# Board1.net
KiCad netlist of a schematic drawn in EasyEDA Pro
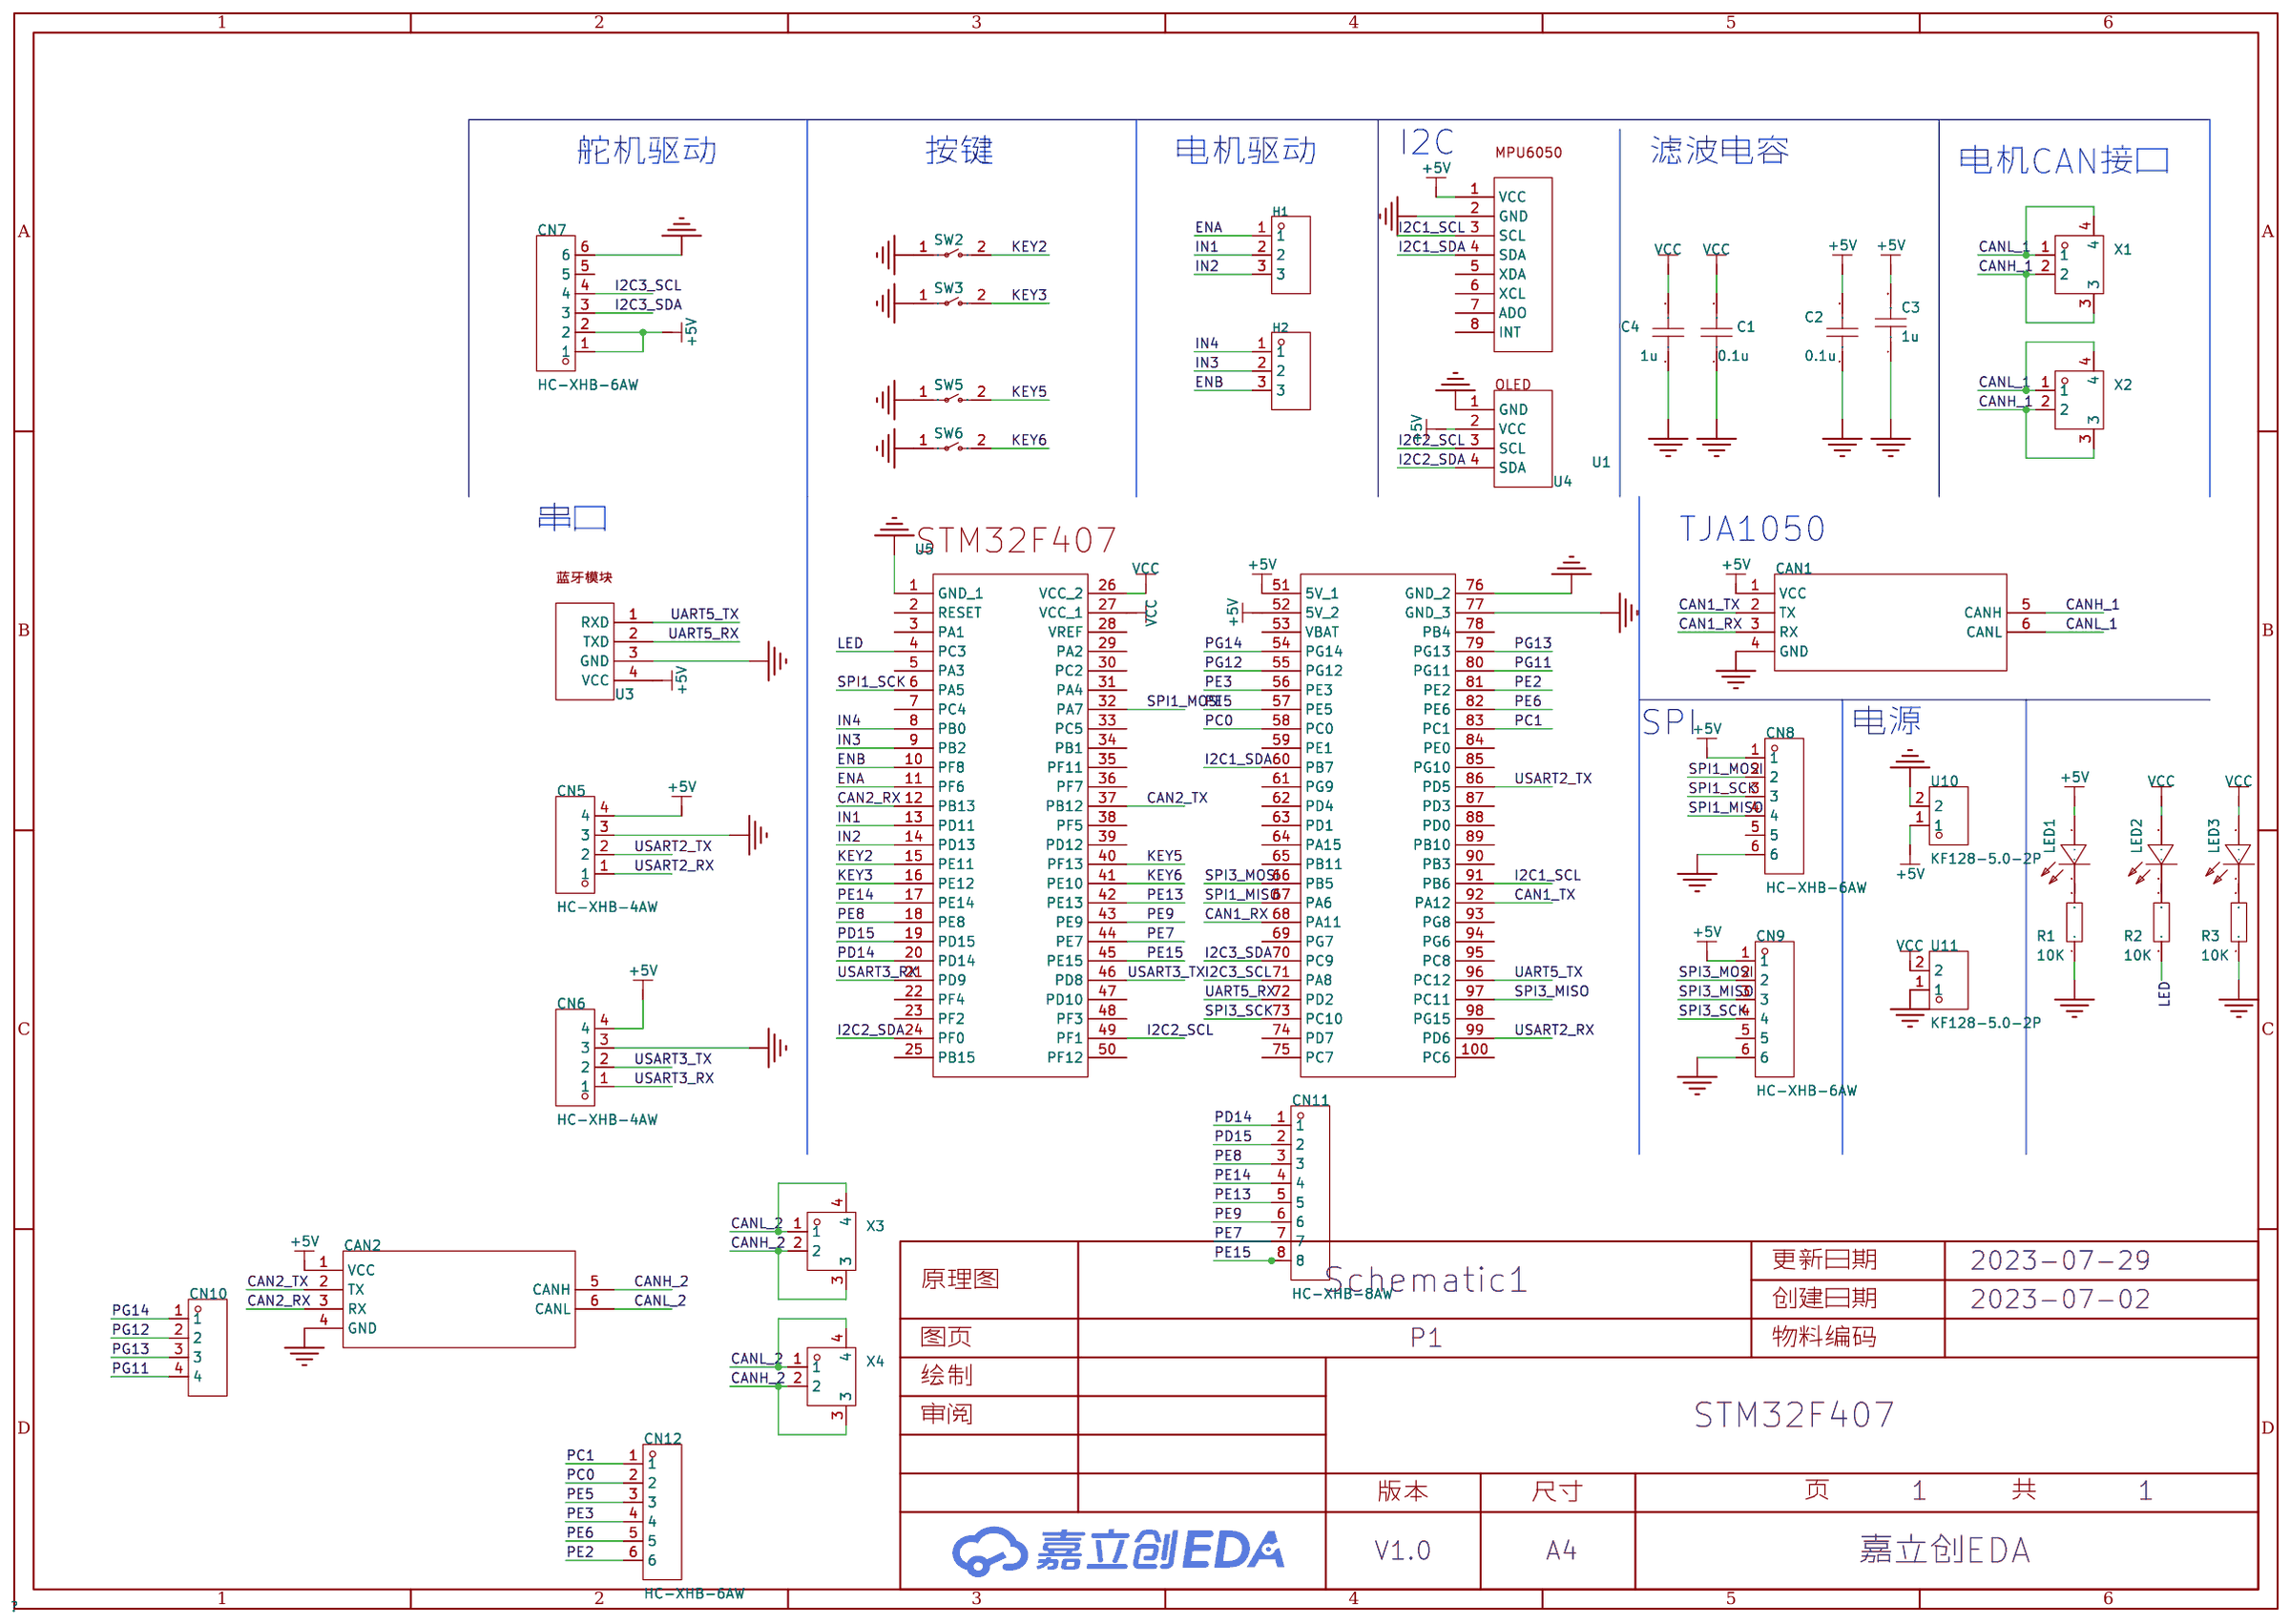
[diagram p0: schematic sheet]

(export (version "E")
  (design (tool "Eeschema 10.0.6"))
  (components
    (comp (ref "C1")
      (value "0.1u")
      (footprint "easyedapro:C0603")
      (libsource (lib "easyedapro") (part "CapAcitance"))
    )
    (comp (ref "C2")
      (value "0.1u")
      (footprint "easyedapro:C0603")
      (libsource (lib "easyedapro") (part "CapAcitance"))
    )
    (comp (ref "C3")
      (value "1u")
      (footprint "easyedapro:C0603")
      (libsource (lib "easyedapro") (part "CapAcitance"))
    )
    (comp (ref "C4")
      (value "1u")
      (footprint "easyedapro:C0603")
      (libsource (lib "easyedapro") (part "CapAcitance"))
    )
    (comp (ref "CAN1")
      (value "~")
      (footprint "easyedapro:CAN模块")
      (libsource (lib "easyedapro") (part "CAN模块"))
    )
    (comp (ref "CAN2")
      (value "~")
      (footprint "easyedapro:CAN模块")
      (libsource (lib "easyedapro") (part "CAN模块"))
    )
    (comp (ref "CN5")
      (value "HC-XHB-4AW")
      (footprint "easyedapro:CONN-TH_4P-P2.5_HCTL_HC-XHB-4AW")
      (description "参考系列:-;间距:2.5mm;插针结构:1x4P;排数:1;每排PIN数:4;行距:-;公母:公型插针;安装方式:弯插;额定电流:3A;工作温度范围:-25°C~+85°C;")
      (fields (field (name "Manufacturer") "HCTL(华灿天禄)"))
      (libsource (lib "easyedapro") (part "HC-XHB-4AW"))
    )
    (comp (ref "CN6")
      (value "HC-XHB-4AW")
      (footprint "easyedapro:CONN-TH_4P-P2.5_HCTL_HC-XHB-4AW")
      (description "参考系列:-;间距:2.5mm;插针结构:1x4P;排数:1;每排PIN数:4;行距:-;公母:公型插针;安装方式:弯插;额定电流:3A;工作温度范围:-25°C~+85°C;")
      (fields (field (name "Manufacturer") "HCTL(华灿天禄)"))
      (libsource (lib "easyedapro") (part "HC-XHB-4AW"))
    )
    (comp (ref "CN7")
      (value "HC-XHB-6AW")
      (footprint "easyedapro:CONN-TH_6P-P2.50_HCTL_HC-XHB-6AW")
      (description "参考系列:-;间距:2.5mm;插针结构:1x6P;排数:1;每排PIN数:6;行距:-;公母:公型插针;安装方式:弯插;额定电流:3A;工作温度范围:-25°C~+85°C;")
      (fields (field (name "Manufacturer") "HCTL(华灿天禄)"))
      (libsource (lib "easyedapro") (part "HC-XHB-6AW"))
    )
    (comp (ref "CN8")
      (value "HC-XHB-6AW")
      (footprint "easyedapro:CONN-TH_6P-P2.50_HCTL_HC-XHB-6AW")
      (description "参考系列:-;间距:2.5mm;插针结构:1x6P;排数:1;每排PIN数:6;行距:-;公母:公型插针;安装方式:弯插;额定电流:3A;工作温度范围:-25°C~+85°C;")
      (fields (field (name "Manufacturer") "HCTL(华灿天禄)"))
      (libsource (lib "easyedapro") (part "HC-XHB-6AW"))
    )
    (comp (ref "CN9")
      (value "HC-XHB-6AW")
      (footprint "easyedapro:CONN-TH_6P-P2.50_HCTL_HC-XHB-6AW")
      (description "参考系列:-;间距:2.5mm;插针结构:1x6P;排数:1;每排PIN数:6;行距:-;公母:公型插针;安装方式:弯插;额定电流:3A;工作温度范围:-25°C~+85°C;")
      (fields (field (name "Manufacturer") "HCTL(华灿天禄)"))
      (libsource (lib "easyedapro") (part "HC-XHB-6AW"))
    )
    (comp (ref "CN10")
      (value "HC-XHB-4AW")
      (footprint "easyedapro:CONN-TH_4P-P2.5_HCTL_HC-XHB-4AW")
      (description "参考系列:-;间距:2.5mm;插针结构:1x4P;排数:1;每排PIN数:4;行距:-;公母:公型插针;安装方式:弯插;额定电流:3A;工作温度范围:-25°C~+85°C;")
      (fields (field (name "Manufacturer") "HCTL(华灿天禄)"))
      (libsource (lib "easyedapro") (part "HC-XHB-4AW"))
    )
    (comp (ref "CN11")
      (value "HC-XHB-8AW")
      (footprint "easyedapro:CONN-TH_HC-XHB-8AW")
      (description "参考系列:-;间距:2.5mm;插针结构:1x8P;排数:1;每排PIN数:8;行距:-;公母:公型插针;安装方式:弯插;额定电流:3A;工作温度范围:-25°C~+85°C;")
      (fields (field (name "Manufacturer") "HCTL(华灿天禄)"))
      (libsource (lib "easyedapro") (part "HC-XHB-8AW"))
    )
    (comp (ref "CN12")
      (value "HC-XHB-6AW")
      (footprint "easyedapro:CONN-TH_6P-P2.50_HCTL_HC-XHB-6AW")
      (description "参考系列:-;间距:2.5mm;插针结构:1x6P;排数:1;每排PIN数:6;行距:-;公母:公型插针;安装方式:弯插;额定电流:3A;工作温度范围:-25°C~+85°C;")
      (fields (field (name "Manufacturer") "HCTL(华灿天禄)"))
      (libsource (lib "easyedapro") (part "HC-XHB-6AW"))
    )
    (comp (ref "H1")
      (value "~")
      (footprint "easyedapro:HDR-TH_3P-P2.54-V-F")
      (libsource (lib "easyedapro") (part "PM254V-11-03-H85"))
    )
    (comp (ref "H2")
      (value "~")
      (footprint "easyedapro:HDR-TH_3P-P2.54-V-F")
      (libsource (lib "easyedapro") (part "PM254V-11-03-H85"))
    )
    (comp (ref "LED1")
      (value "NCD0805R1")
      (footprint "easyedapro:LED0805-RD_RED")
      (description "发光颜色:红灯;")
      (fields (field (name "Manufacturer") "国星光电"))
      (libsource (lib "easyedapro") (part "FC-2012HRK-620D"))
    )
    (comp (ref "LED2")
      (value "NCD0805R1")
      (footprint "easyedapro:LED0805-RD_RED")
      (description "发光颜色:红灯;")
      (fields (field (name "Manufacturer") "国星光电"))
      (libsource (lib "easyedapro") (part "FC-2012HRK-620D"))
    )
    (comp (ref "LED3")
      (value "NCD0805R1")
      (footprint "easyedapro:LED0805-RD_RED")
      (description "发光颜色:红灯;")
      (fields (field (name "Manufacturer") "国星光电"))
      (libsource (lib "easyedapro") (part "FC-2012HRK-620D"))
    )
    (comp (ref "R1") (value "10K") (footprint "easyedapro:R0603") (libsource (lib "easyedapro") (part "电阻")))
    (comp (ref "R2") (value "10K") (footprint "easyedapro:R0603") (libsource (lib "easyedapro") (part "电阻")))
    (comp (ref "R3") (value "10K") (footprint "easyedapro:R0603") (libsource (lib "easyedapro") (part "电阻")))
    (comp (ref "SW2")
      (value "TS-1007S-AR02516")
      (footprint "easyedapro:SW-SMD_L6.1-W3.6-LS7.9")
      (description "触点电流:50mA;额定电压(DC):12V;绝缘电阻:100MΩ;电路结构:单刀单掷;安装方式:立贴;作用力:160gf@±50gf;机械寿命:5万次;带支架:否;")
      (fields (field (name "Manufacturer") "XUNPU(讯普)"))
      (libsource (lib "easyedapro") (part "TS-1007S-AR02516"))
    )
    (comp (ref "SW3")
      (value "TS-1007S-AR02516")
      (footprint "easyedapro:SW-SMD_L6.1-W3.6-LS7.9")
      (description "触点电流:50mA;额定电压(DC):12V;绝缘电阻:100MΩ;电路结构:单刀单掷;安装方式:立贴;作用力:160gf@±50gf;机械寿命:5万次;带支架:否;")
      (fields (field (name "Manufacturer") "XUNPU(讯普)"))
      (libsource (lib "easyedapro") (part "TS-1007S-AR02516"))
    )
    (comp (ref "SW5")
      (value "TS-1007S-AR02516")
      (footprint "easyedapro:SW-SMD_L6.1-W3.6-LS7.9")
      (description "触点电流:50mA;额定电压(DC):12V;绝缘电阻:100MΩ;电路结构:单刀单掷;安装方式:立贴;作用力:160gf@±50gf;机械寿命:5万次;带支架:否;")
      (fields (field (name "Manufacturer") "XUNPU(讯普)"))
      (libsource (lib "easyedapro") (part "TS-1007S-AR02516"))
    )
    (comp (ref "SW6")
      (value "TS-1007S-AR02516")
      (footprint "easyedapro:SW-SMD_L6.1-W3.6-LS7.9")
      (description "触点电流:50mA;额定电压(DC):12V;绝缘电阻:100MΩ;电路结构:单刀单掷;安装方式:立贴;作用力:160gf@±50gf;机械寿命:5万次;带支架:否;")
      (fields (field (name "Manufacturer") "XUNPU(讯普)"))
      (libsource (lib "easyedapro") (part "TS-1007S-AR02516"))
    )
    (comp (ref "U1")
      (value "~")
      (footprint "easyedapro:MPU6050")
      (libsource (lib "easyedapro") (part "MPU6050"))
    )
    (comp (ref "U3") (value "~") (footprint "easyedapro:蓝牙模块") (libsource (lib "easyedapro") (part "蓝牙模块")))
    (comp (ref "U4") (value "~") (footprint "easyedapro:OLED") (libsource (lib "easyedapro") (part "OLED")))
    (comp (ref "U5")
      (value "~")
      (footprint "easyedapro:CORE BORED")
      (libsource (lib "easyedapro") (part "CORE BORED"))
    )
    (comp (ref "U10")
      (value "KF128-5.0-2P")
      (footprint "easyedapro:CONN-TH_P5.00_KF128-5.0-2P")
      (fields (field (name "Manufacturer") "KEFA(科发)"))
      (libsource (lib "easyedapro") (part "KF128-5.0-2P"))
    )
    (comp (ref "U11")
      (value "KF128-5.0-2P")
      (footprint "easyedapro:CONN-TH_P5.00_KF128-5.0-2P")
      (fields (field (name "Manufacturer") "KEFA(科发)"))
      (libsource (lib "easyedapro") (part "KF128-5.0-2P"))
    )
    (comp (ref "X1")
      (value "GH125-S02DCA-00")
      (footprint "easyedapro:CONN-SMD_2P-P1.25_JUSHUO_GH125-S02DCA-00")
      (description "参考系列:-;间距:1.25mm;插针结构:1x2P;排数:1;每排PIN数:2;行距:-;公母:公型插针;安装方式:卧贴;额定电流:1A;工作温度范围:-25°C~+85°C;")
      (fields (field (name "Manufacturer") "JS(钜硕电子)"))
      (libsource (lib "easyedapro") (part "GH125-S02DCA-00"))
    )
    (comp (ref "X2")
      (value "GH125-S02DCA-00")
      (footprint "easyedapro:CONN-SMD_2P-P1.25_JUSHUO_GH125-S02DCA-00")
      (description "参考系列:-;间距:1.25mm;插针结构:1x2P;排数:1;每排PIN数:2;行距:-;公母:公型插针;安装方式:卧贴;额定电流:1A;工作温度范围:-25°C~+85°C;")
      (fields (field (name "Manufacturer") "JS(钜硕电子)"))
      (libsource (lib "easyedapro") (part "GH125-S02DCA-00"))
    )
    (comp (ref "X3")
      (value "GH125-S02DCA-00")
      (footprint "easyedapro:CONN-SMD_2P-P1.25_JUSHUO_GH125-S02DCA-00")
      (description "参考系列:-;间距:1.25mm;插针结构:1x2P;排数:1;每排PIN数:2;行距:-;公母:公型插针;安装方式:卧贴;额定电流:1A;工作温度范围:-25°C~+85°C;")
      (fields (field (name "Manufacturer") "JS(钜硕电子)"))
      (libsource (lib "easyedapro") (part "GH125-S02DCA-00"))
    )
    (comp (ref "X4")
      (value "GH125-S02DCA-00")
      (footprint "easyedapro:CONN-SMD_2P-P1.25_JUSHUO_GH125-S02DCA-00")
      (description "参考系列:-;间距:1.25mm;插针结构:1x2P;排数:1;每排PIN数:2;行距:-;公母:公型插针;安装方式:卧贴;额定电流:1A;工作温度范围:-25°C~+85°C;")
      (fields (field (name "Manufacturer") "JS(钜硕电子)"))
      (libsource (lib "easyedapro") (part "GH125-S02DCA-00"))
    )
  )
  (nets
    (net (code "1") (name "+5V") (class "Default")
      (node (ref "C2") (pin "2") (pinfunction "2_2") (pintype "input"))
      (node (ref "C3") (pin "2") (pinfunction "2_2") (pintype "input"))
      (node (ref "CAN1") (pin "1") (pinfunction "VCC_1") (pintype "input"))
      (node (ref "CAN2") (pin "1") (pinfunction "VCC_1") (pintype "input"))
      (node (ref "CN5") (pin "4") (pinfunction "4_4") (pintype "input"))
      (node (ref "CN6") (pin "4") (pinfunction "4_4") (pintype "input"))
      (node (ref "CN7") (pin "1") (pinfunction "1_1") (pintype "input"))
      (node (ref "CN7") (pin "2") (pinfunction "2_2") (pintype "input"))
      (node (ref "CN8") (pin "1") (pinfunction "1_1") (pintype "input"))
      (node (ref "CN9") (pin "1") (pinfunction "1_1") (pintype "input"))
      (node (ref "LED1") (pin "2") (pinfunction "+_2") (pintype "input"))
      (node (ref "U1") (pin "1") (pinfunction "VCC_1") (pintype "input"))
      (node (ref "U10") (pin "1") (pinfunction "1_1") (pintype "input"))
      (node (ref "U3") (pin "4") (pinfunction "VCC_4") (pintype "input"))
      (node (ref "U4") (pin "2") (pinfunction "VCC_2") (pintype "input"))
      (node (ref "U5") (pin "51") (pinfunction "5V_1_51") (pintype "input"))
      (node (ref "U5") (pin "52") (pinfunction "5V_2_52") (pintype "input"))
    )
    (net (code "2") (name "/CAN1_RX") (class "Default")
      (node (ref "CAN1") (pin "3") (pinfunction "RX_3") (pintype "input"))
      (node (ref "U5") (pin "68") (pinfunction "PA11_68") (pintype "input"))
    )
    (net (code "3") (name "/CAN1_TX") (class "Default")
      (node (ref "CAN1") (pin "2") (pinfunction "TX_2") (pintype "input"))
      (node (ref "U5") (pin "92") (pinfunction "PA12_92") (pintype "input"))
    )
    (net (code "4") (name "/CAN2_RX") (class "Default")
      (node (ref "CAN2") (pin "3") (pinfunction "RX_3") (pintype "input"))
      (node (ref "U5") (pin "12") (pinfunction "PB13_12") (pintype "input"))
    )
    (net (code "5") (name "/CAN2_TX") (class "Default")
      (node (ref "CAN2") (pin "2") (pinfunction "TX_2") (pintype "input"))
      (node (ref "U5") (pin "37") (pinfunction "PB12_37") (pintype "input"))
    )
    (net (code "6") (name "/CANH_1") (class "Default")
      (node (ref "CAN1") (pin "5") (pinfunction "CANH_5") (pintype "input"))
      (node (ref "X1") (pin "2") (pinfunction "2_2") (pintype "input"))
      (node (ref "X1") (pin "3") (pinfunction "3_3") (pintype "input"))
      (node (ref "X2") (pin "2") (pinfunction "2_2") (pintype "input"))
      (node (ref "X2") (pin "3") (pinfunction "3_3") (pintype "input"))
    )
    (net (code "7") (name "/CANH_2") (class "Default")
      (node (ref "CAN2") (pin "5") (pinfunction "CANH_5") (pintype "input"))
      (node (ref "X3") (pin "2") (pinfunction "2_2") (pintype "input"))
      (node (ref "X3") (pin "3") (pinfunction "3_3") (pintype "input"))
      (node (ref "X4") (pin "2") (pinfunction "2_2") (pintype "input"))
      (node (ref "X4") (pin "3") (pinfunction "3_3") (pintype "input"))
    )
    (net (code "8") (name "/CANL_1") (class "Default")
      (node (ref "CAN1") (pin "6") (pinfunction "CANL_6") (pintype "input"))
      (node (ref "X1") (pin "1") (pinfunction "1_1") (pintype "input"))
      (node (ref "X1") (pin "4") (pinfunction "4_4") (pintype "input"))
      (node (ref "X2") (pin "1") (pinfunction "1_1") (pintype "input"))
      (node (ref "X2") (pin "4") (pinfunction "4_4") (pintype "input"))
    )
    (net (code "9") (name "/CANL_2") (class "Default")
      (node (ref "CAN2") (pin "6") (pinfunction "CANL_6") (pintype "input"))
      (node (ref "X3") (pin "1") (pinfunction "1_1") (pintype "input"))
      (node (ref "X3") (pin "4") (pinfunction "4_4") (pintype "input"))
      (node (ref "X4") (pin "1") (pinfunction "1_1") (pintype "input"))
      (node (ref "X4") (pin "4") (pinfunction "4_4") (pintype "input"))
    )
    (net (code "10") (name "/ENA") (class "Default")
      (node (ref "H1") (pin "1") (pinfunction "1_1") (pintype "input"))
      (node (ref "U5") (pin "11") (pinfunction "PF6_11") (pintype "input"))
    )
    (net (code "11") (name "/ENB") (class "Default")
      (node (ref "H2") (pin "3") (pinfunction "3_3") (pintype "input"))
      (node (ref "U5") (pin "10") (pinfunction "PF8_10") (pintype "input"))
    )
    (net (code "12") (name "/I2C1_SCL") (class "Default")
      (node (ref "U1") (pin "3") (pinfunction "SCL_3") (pintype "input"))
      (node (ref "U5") (pin "91") (pinfunction "PB6_91") (pintype "input"))
    )
    (net (code "13") (name "/I2C1_SDA") (class "Default")
      (node (ref "U1") (pin "4") (pinfunction "SDA_4") (pintype "input"))
      (node (ref "U5") (pin "60") (pinfunction "PB7_60") (pintype "input"))
    )
    (net (code "14") (name "/I2C2_SCL") (class "Default")
      (node (ref "U4") (pin "3") (pinfunction "SCL_3") (pintype "input"))
      (node (ref "U5") (pin "49") (pinfunction "PF1_49") (pintype "input"))
    )
    (net (code "15") (name "/I2C2_SDA") (class "Default")
      (node (ref "U4") (pin "4") (pinfunction "SDA_4") (pintype "input"))
      (node (ref "U5") (pin "24") (pinfunction "PF0_24") (pintype "input"))
    )
    (net (code "16") (name "/I2C3_SCL") (class "Default")
      (node (ref "CN7") (pin "4") (pinfunction "4_4") (pintype "input"))
      (node (ref "U5") (pin "71") (pinfunction "PA8_71") (pintype "input"))
    )
    (net (code "17") (name "/I2C3_SDA") (class "Default")
      (node (ref "CN7") (pin "3") (pinfunction "3_3") (pintype "input"))
      (node (ref "U5") (pin "70") (pinfunction "PC9_70") (pintype "input"))
    )
    (net (code "18") (name "/IN1") (class "Default")
      (node (ref "H1") (pin "2") (pinfunction "2_2") (pintype "input"))
      (node (ref "U5") (pin "13") (pinfunction "PD11_13") (pintype "input"))
    )
    (net (code "19") (name "/IN2") (class "Default")
      (node (ref "H1") (pin "3") (pinfunction "3_3") (pintype "input"))
      (node (ref "U5") (pin "14") (pinfunction "PD13_14") (pintype "input"))
    )
    (net (code "20") (name "/IN3") (class "Default")
      (node (ref "H2") (pin "2") (pinfunction "2_2") (pintype "input"))
      (node (ref "U5") (pin "9") (pinfunction "PB2_9") (pintype "input"))
    )
    (net (code "21") (name "/IN4") (class "Default")
      (node (ref "H2") (pin "1") (pinfunction "1_1") (pintype "input"))
      (node (ref "U5") (pin "8") (pinfunction "PB0_8") (pintype "input"))
    )
    (net (code "22") (name "/KEY2") (class "Default")
      (node (ref "SW2") (pin "2") (pinfunction "2_2") (pintype "input"))
      (node (ref "U5") (pin "15") (pinfunction "PE11_15") (pintype "input"))
    )
    (net (code "23") (name "/KEY3") (class "Default")
      (node (ref "SW3") (pin "2") (pinfunction "2_2") (pintype "input"))
      (node (ref "U5") (pin "16") (pinfunction "PE12_16") (pintype "input"))
    )
    (net (code "24") (name "/KEY5") (class "Default")
      (node (ref "SW5") (pin "2") (pinfunction "2_2") (pintype "input"))
      (node (ref "U5") (pin "40") (pinfunction "PF13_40") (pintype "input"))
    )
    (net (code "25") (name "/KEY6") (class "Default")
      (node (ref "SW6") (pin "2") (pinfunction "2_2") (pintype "input"))
      (node (ref "U5") (pin "41") (pinfunction "PE10_41") (pintype "input"))
    )
    (net (code "26") (name "/LED") (class "Default")
      (node (ref "R2") (pin "1") (pinfunction "1_1") (pintype "input"))
      (node (ref "U5") (pin "4") (pinfunction "PC3_4") (pintype "input"))
    )
    (net (code "27") (name "/PC0") (class "Default")
      (node (ref "CN12") (pin "2") (pinfunction "2_2") (pintype "input"))
      (node (ref "U5") (pin "58") (pinfunction "PC0_58") (pintype "input"))
    )
    (net (code "28") (name "/PC1") (class "Default")
      (node (ref "CN12") (pin "1") (pinfunction "1_1") (pintype "input"))
      (node (ref "U5") (pin "83") (pinfunction "PC1_83") (pintype "input"))
    )
    (net (code "29") (name "/PD14") (class "Default")
      (node (ref "CN11") (pin "1") (pinfunction "1_1") (pintype "input"))
      (node (ref "U5") (pin "20") (pinfunction "PD14_20") (pintype "input"))
    )
    (net (code "30") (name "/PD15") (class "Default")
      (node (ref "CN11") (pin "2") (pinfunction "2_2") (pintype "input"))
      (node (ref "U5") (pin "19") (pinfunction "PD15_19") (pintype "input"))
    )
    (net (code "31") (name "/PE2") (class "Default")
      (node (ref "CN12") (pin "6") (pinfunction "6_6") (pintype "input"))
      (node (ref "U5") (pin "81") (pinfunction "PE2_81") (pintype "input"))
    )
    (net (code "32") (name "/PE3") (class "Default")
      (node (ref "CN12") (pin "4") (pinfunction "4_4") (pintype "input"))
      (node (ref "U5") (pin "56") (pinfunction "PE3_56") (pintype "input"))
    )
    (net (code "33") (name "/PE5") (class "Default")
      (node (ref "CN12") (pin "3") (pinfunction "3_3") (pintype "input"))
      (node (ref "U5") (pin "57") (pinfunction "PE5_57") (pintype "input"))
    )
    (net (code "34") (name "/PE6") (class "Default")
      (node (ref "CN12") (pin "5") (pinfunction "5_5") (pintype "input"))
      (node (ref "U5") (pin "82") (pinfunction "PE6_82") (pintype "input"))
    )
    (net (code "35") (name "/PE7") (class "Default")
      (node (ref "CN11") (pin "7") (pinfunction "7_7") (pintype "input"))
      (node (ref "U5") (pin "44") (pinfunction "PE7_44") (pintype "input"))
    )
    (net (code "36") (name "/PE8") (class "Default")
      (node (ref "CN11") (pin "3") (pinfunction "3_3") (pintype "input"))
      (node (ref "U5") (pin "18") (pinfunction "PE8_18") (pintype "input"))
    )
    (net (code "37") (name "/PE9") (class "Default")
      (node (ref "CN11") (pin "6") (pinfunction "6_6") (pintype "input"))
      (node (ref "U5") (pin "43") (pinfunction "PE9_43") (pintype "input"))
    )
    (net (code "38") (name "/PE13") (class "Default")
      (node (ref "CN11") (pin "5") (pinfunction "5_5") (pintype "input"))
      (node (ref "U5") (pin "42") (pinfunction "PE13_42") (pintype "input"))
    )
    (net (code "39") (name "/PE14") (class "Default")
      (node (ref "CN11") (pin "4") (pinfunction "4_4") (pintype "input"))
      (node (ref "U5") (pin "17") (pinfunction "PE14_17") (pintype "input"))
    )
    (net (code "40") (name "/PE15") (class "Default")
      (node (ref "CN11") (pin "8") (pinfunction "8_8") (pintype "input"))
      (node (ref "U5") (pin "45") (pinfunction "PE15_45") (pintype "input"))
    )
    (net (code "41") (name "/PG11") (class "Default")
      (node (ref "CN10") (pin "4") (pinfunction "4_4") (pintype "input"))
      (node (ref "U5") (pin "80") (pinfunction "PG11_80") (pintype "input"))
    )
    (net (code "42") (name "/PG12") (class "Default")
      (node (ref "CN10") (pin "2") (pinfunction "2_2") (pintype "input"))
      (node (ref "U5") (pin "55") (pinfunction "PG12_55") (pintype "input"))
    )
    (net (code "43") (name "/PG13") (class "Default")
      (node (ref "CN10") (pin "3") (pinfunction "3_3") (pintype "input"))
      (node (ref "U5") (pin "79") (pinfunction "PG13_79") (pintype "input"))
    )
    (net (code "44") (name "/PG14") (class "Default")
      (node (ref "CN10") (pin "1") (pinfunction "1_1") (pintype "input"))
      (node (ref "U5") (pin "54") (pinfunction "PG14_54") (pintype "input"))
    )
    (net (code "45") (name "/SPI1_MISO") (class "Default")
      (node (ref "CN8") (pin "4") (pinfunction "4_4") (pintype "input"))
      (node (ref "U5") (pin "67") (pinfunction "PA6_67") (pintype "input"))
    )
    (net (code "46") (name "/SPI1_MOSI") (class "Default")
      (node (ref "CN8") (pin "2") (pinfunction "2_2") (pintype "input"))
      (node (ref "U5") (pin "32") (pinfunction "PA7_32") (pintype "input"))
    )
    (net (code "47") (name "/SPI1_SCK") (class "Default")
      (node (ref "CN8") (pin "3") (pinfunction "3_3") (pintype "input"))
      (node (ref "U5") (pin "6") (pinfunction "PA5_6") (pintype "input"))
    )
    (net (code "48") (name "/SPI3_MISO") (class "Default")
      (node (ref "CN9") (pin "3") (pinfunction "3_3") (pintype "input"))
      (node (ref "U5") (pin "97") (pinfunction "PC11_97") (pintype "input"))
    )
    (net (code "49") (name "/SPI3_MOSI") (class "Default")
      (node (ref "CN9") (pin "2") (pinfunction "2_2") (pintype "input"))
      (node (ref "U5") (pin "66") (pinfunction "PB5_66") (pintype "input"))
    )
    (net (code "50") (name "/SPI3_SCK") (class "Default")
      (node (ref "CN9") (pin "4") (pinfunction "4_4") (pintype "input"))
      (node (ref "U5") (pin "73") (pinfunction "PC10_73") (pintype "input"))
    )
    (net (code "51") (name "/UART5_RX") (class "Default")
      (node (ref "U3") (pin "2") (pinfunction "TXD_2") (pintype "input"))
      (node (ref "U5") (pin "72") (pinfunction "PD2_72") (pintype "input"))
    )
    (net (code "52") (name "/UART5_TX") (class "Default")
      (node (ref "U3") (pin "1") (pinfunction "RXD_1") (pintype "input"))
      (node (ref "U5") (pin "96") (pinfunction "PC12_96") (pintype "input"))
    )
    (net (code "53") (name "/USART2_RX") (class "Default")
      (node (ref "CN5") (pin "1") (pinfunction "1_1") (pintype "input"))
      (node (ref "U5") (pin "99") (pinfunction "PD6_99") (pintype "input"))
    )
    (net (code "54") (name "/USART2_TX") (class "Default")
      (node (ref "CN5") (pin "2") (pinfunction "2_2") (pintype "input"))
      (node (ref "U5") (pin "86") (pinfunction "PD5_86") (pintype "input"))
    )
    (net (code "55") (name "/USART3_RX") (class "Default")
      (node (ref "CN6") (pin "1") (pinfunction "1_1") (pintype "input"))
      (node (ref "U5") (pin "21") (pinfunction "PD9_21") (pintype "input"))
    )
    (net (code "56") (name "/USART3_TX") (class "Default")
      (node (ref "CN6") (pin "2") (pinfunction "2_2") (pintype "input"))
      (node (ref "U5") (pin "46") (pinfunction "PD8_46") (pintype "input"))
    )
    (net (code "57") (name "GND") (class "Default")
      (node (ref "C1") (pin "1") (pinfunction "1_1") (pintype "input"))
      (node (ref "C2") (pin "1") (pinfunction "1_1") (pintype "input"))
      (node (ref "C3") (pin "1") (pinfunction "1_1") (pintype "input"))
      (node (ref "C4") (pin "1") (pinfunction "1_1") (pintype "input"))
      (node (ref "CAN1") (pin "4") (pinfunction "GND_4") (pintype "input"))
      (node (ref "CAN2") (pin "4") (pinfunction "GND_4") (pintype "input"))
      (node (ref "CN5") (pin "3") (pinfunction "3_3") (pintype "input"))
      (node (ref "CN6") (pin "3") (pinfunction "3_3") (pintype "input"))
      (node (ref "CN7") (pin "6") (pinfunction "6_6") (pintype "input"))
      (node (ref "CN8") (pin "6") (pinfunction "6_6") (pintype "input"))
      (node (ref "CN9") (pin "6") (pinfunction "6_6") (pintype "input"))
      (node (ref "R1") (pin "1") (pinfunction "1_1") (pintype "input"))
      (node (ref "R3") (pin "1") (pinfunction "1_1") (pintype "input"))
      (node (ref "SW2") (pin "1") (pinfunction "1_1") (pintype "input"))
      (node (ref "SW3") (pin "1") (pinfunction "1_1") (pintype "input"))
      (node (ref "SW5") (pin "1") (pinfunction "1_1") (pintype "input"))
      (node (ref "SW6") (pin "1") (pinfunction "1_1") (pintype "input"))
      (node (ref "U1") (pin "2") (pinfunction "GND_2") (pintype "input"))
      (node (ref "U10") (pin "2") (pinfunction "2_2") (pintype "input"))
      (node (ref "U11") (pin "1") (pinfunction "1_1") (pintype "input"))
      (node (ref "U3") (pin "3") (pinfunction "GND_3") (pintype "input"))
      (node (ref "U4") (pin "1") (pinfunction "GND_1") (pintype "input"))
      (node (ref "U5") (pin "1") (pinfunction "GND_1_1") (pintype "input"))
      (node (ref "U5") (pin "76") (pinfunction "GND_2_76") (pintype "input"))
      (node (ref "U5") (pin "77") (pinfunction "GND_3_77") (pintype "input"))
    )
    (net (code "58") (name "Net-(LED1--)") (class "Default")
      (node (ref "LED1") (pin "1") (pinfunction "-_1") (pintype "input"))
      (node (ref "R1") (pin "2") (pinfunction "2_2") (pintype "input"))
    )
    (net (code "59") (name "Net-(LED2--)") (class "Default")
      (node (ref "LED2") (pin "1") (pinfunction "-_1") (pintype "input"))
      (node (ref "R2") (pin "2") (pinfunction "2_2") (pintype "input"))
    )
    (net (code "60") (name "Net-(LED3--)") (class "Default")
      (node (ref "LED3") (pin "1") (pinfunction "-_1") (pintype "input"))
      (node (ref "R3") (pin "2") (pinfunction "2_2") (pintype "input"))
    )
    (net (code "61") (name "VCC") (class "Default")
      (node (ref "C1") (pin "2") (pinfunction "2_2") (pintype "input"))
      (node (ref "C4") (pin "2") (pinfunction "2_2") (pintype "input"))
      (node (ref "LED2") (pin "2") (pinfunction "+_2") (pintype "input"))
      (node (ref "LED3") (pin "2") (pinfunction "+_2") (pintype "input"))
      (node (ref "U11") (pin "2") (pinfunction "2_2") (pintype "input"))
      (node (ref "U5") (pin "26") (pinfunction "VCC_2_26") (pintype "input"))
      (node (ref "U5") (pin "27") (pinfunction "VCC_1_27") (pintype "input"))
    )
    (net (code "62") (name "unconnected-(CN7-Pad5)") (class "Default")
      (node (ref "CN7") (pin "5") (pinfunction "5_5") (pintype "input"))
    )
    (net (code "63") (name "unconnected-(CN8-Pad5)") (class "Default")
      (node (ref "CN8") (pin "5") (pinfunction "5_5") (pintype "input"))
    )
    (net (code "64") (name "unconnected-(CN9-Pad5)") (class "Default")
      (node (ref "CN9") (pin "5") (pinfunction "5_5") (pintype "input"))
    )
    (net (code "65") (name "unconnected-(U1-ADO-Pad7)") (class "Default")
      (node (ref "U1") (pin "7") (pinfunction "ADO_7") (pintype "input"))
    )
    (net (code "66") (name "unconnected-(U1-INT-Pad8)") (class "Default")
      (node (ref "U1") (pin "8") (pinfunction "INT_8") (pintype "input"))
    )
    (net (code "67") (name "unconnected-(U1-XCL-Pad6)") (class "Default")
      (node (ref "U1") (pin "6") (pinfunction "XCL_6") (pintype "input"))
    )
    (net (code "68") (name "unconnected-(U1-XDA-Pad5)") (class "Default")
      (node (ref "U1") (pin "5") (pinfunction "XDA_5") (pintype "input"))
    )
    (net (code "69") (name "unconnected-(U5-PA1-Pad3)") (class "Default")
      (node (ref "U5") (pin "3") (pinfunction "PA1_3") (pintype "input"))
    )
    (net (code "70") (name "unconnected-(U5-PA2-Pad29)") (class "Default")
      (node (ref "U5") (pin "29") (pinfunction "PA2_29") (pintype "input"))
    )
    (net (code "71") (name "unconnected-(U5-PA3-Pad5)") (class "Default")
      (node (ref "U5") (pin "5") (pinfunction "PA3_5") (pintype "input"))
    )
    (net (code "72") (name "unconnected-(U5-PA4-Pad31)") (class "Default")
      (node (ref "U5") (pin "31") (pinfunction "PA4_31") (pintype "input"))
    )
    (net (code "73") (name "unconnected-(U5-PA15-Pad64)") (class "Default")
      (node (ref "U5") (pin "64") (pinfunction "PA15_64") (pintype "input"))
    )
    (net (code "74") (name "unconnected-(U5-PB1-Pad34)") (class "Default")
      (node (ref "U5") (pin "34") (pinfunction "PB1_34") (pintype "input"))
    )
    (net (code "75") (name "unconnected-(U5-PB3-Pad90)") (class "Default")
      (node (ref "U5") (pin "90") (pinfunction "PB3_90") (pintype "input"))
    )
    (net (code "76") (name "unconnected-(U5-PB4-Pad78)") (class "Default")
      (node (ref "U5") (pin "78") (pinfunction "PB4_78") (pintype "input"))
    )
    (net (code "77") (name "unconnected-(U5-PB10-Pad89)") (class "Default")
      (node (ref "U5") (pin "89") (pinfunction "PB10_89") (pintype "input"))
    )
    (net (code "78") (name "unconnected-(U5-PB11-Pad65)") (class "Default")
      (node (ref "U5") (pin "65") (pinfunction "PB11_65") (pintype "input"))
    )
    (net (code "79") (name "unconnected-(U5-PB15-Pad25)") (class "Default")
      (node (ref "U5") (pin "25") (pinfunction "PB15_25") (pintype "input"))
    )
    (net (code "80") (name "unconnected-(U5-PC2-Pad30)") (class "Default")
      (node (ref "U5") (pin "30") (pinfunction "PC2_30") (pintype "input"))
    )
    (net (code "81") (name "unconnected-(U5-PC4-Pad7)") (class "Default")
      (node (ref "U5") (pin "7") (pinfunction "PC4_7") (pintype "input"))
    )
    (net (code "82") (name "unconnected-(U5-PC5-Pad33)") (class "Default")
      (node (ref "U5") (pin "33") (pinfunction "PC5_33") (pintype "input"))
    )
    (net (code "83") (name "unconnected-(U5-PC6-Pad100)") (class "Default")
      (node (ref "U5") (pin "100") (pinfunction "PC6_100") (pintype "input"))
    )
    (net (code "84") (name "unconnected-(U5-PC7-Pad75)") (class "Default")
      (node (ref "U5") (pin "75") (pinfunction "PC7_75") (pintype "input"))
    )
    (net (code "85") (name "unconnected-(U5-PC8-Pad95)") (class "Default")
      (node (ref "U5") (pin "95") (pinfunction "PC8_95") (pintype "input"))
    )
    (net (code "86") (name "unconnected-(U5-PD0-Pad88)") (class "Default")
      (node (ref "U5") (pin "88") (pinfunction "PD0_88") (pintype "input"))
    )
    (net (code "87") (name "unconnected-(U5-PD1-Pad63)") (class "Default")
      (node (ref "U5") (pin "63") (pinfunction "PD1_63") (pintype "input"))
    )
    (net (code "88") (name "unconnected-(U5-PD3-Pad87)") (class "Default")
      (node (ref "U5") (pin "87") (pinfunction "PD3_87") (pintype "input"))
    )
    (net (code "89") (name "unconnected-(U5-PD4-Pad62)") (class "Default")
      (node (ref "U5") (pin "62") (pinfunction "PD4_62") (pintype "input"))
    )
    (net (code "90") (name "unconnected-(U5-PD7-Pad74)") (class "Default")
      (node (ref "U5") (pin "74") (pinfunction "PD7_74") (pintype "input"))
    )
    (net (code "91") (name "unconnected-(U5-PD10-Pad47)") (class "Default")
      (node (ref "U5") (pin "47") (pinfunction "PD10_47") (pintype "input"))
    )
    (net (code "92") (name "unconnected-(U5-PD12-Pad39)") (class "Default")
      (node (ref "U5") (pin "39") (pinfunction "PD12_39") (pintype "input"))
    )
    (net (code "93") (name "unconnected-(U5-PE0-Pad84)") (class "Default")
      (node (ref "U5") (pin "84") (pinfunction "PE0_84") (pintype "input"))
    )
    (net (code "94") (name "unconnected-(U5-PE1-Pad59)") (class "Default")
      (node (ref "U5") (pin "59") (pinfunction "PE1_59") (pintype "input"))
    )
    (net (code "95") (name "unconnected-(U5-PF2-Pad23)") (class "Default")
      (node (ref "U5") (pin "23") (pinfunction "PF2_23") (pintype "input"))
    )
    (net (code "96") (name "unconnected-(U5-PF3-Pad48)") (class "Default")
      (node (ref "U5") (pin "48") (pinfunction "PF3_48") (pintype "input"))
    )
    (net (code "97") (name "unconnected-(U5-PF4-Pad22)") (class "Default")
      (node (ref "U5") (pin "22") (pinfunction "PF4_22") (pintype "input"))
    )
    (net (code "98") (name "unconnected-(U5-PF5-Pad38)") (class "Default")
      (node (ref "U5") (pin "38") (pinfunction "PF5_38") (pintype "input"))
    )
    (net (code "99") (name "unconnected-(U5-PF7-Pad36)") (class "Default")
      (node (ref "U5") (pin "36") (pinfunction "PF7_36") (pintype "input"))
    )
    (net (code "100") (name "unconnected-(U5-PF11-Pad35)") (class "Default")
      (node (ref "U5") (pin "35") (pinfunction "PF11_35") (pintype "input"))
    )
    (net (code "101") (name "unconnected-(U5-PF12-Pad50)") (class "Default")
      (node (ref "U5") (pin "50") (pinfunction "PF12_50") (pintype "input"))
    )
    (net (code "102") (name "unconnected-(U5-PG6-Pad94)") (class "Default")
      (node (ref "U5") (pin "94") (pinfunction "PG6_94") (pintype "input"))
    )
    (net (code "103") (name "unconnected-(U5-PG7-Pad69)") (class "Default")
      (node (ref "U5") (pin "69") (pinfunction "PG7_69") (pintype "input"))
    )
    (net (code "104") (name "unconnected-(U5-PG8-Pad93)") (class "Default")
      (node (ref "U5") (pin "93") (pinfunction "PG8_93") (pintype "input"))
    )
    (net (code "105") (name "unconnected-(U5-PG9-Pad61)") (class "Default")
      (node (ref "U5") (pin "61") (pinfunction "PG9_61") (pintype "input"))
    )
    (net (code "106") (name "unconnected-(U5-PG10-Pad85)") (class "Default")
      (node (ref "U5") (pin "85") (pinfunction "PG10_85") (pintype "input"))
    )
    (net (code "107") (name "unconnected-(U5-PG15-Pad98)") (class "Default")
      (node (ref "U5") (pin "98") (pinfunction "PG15_98") (pintype "input"))
    )
    (net (code "108") (name "unconnected-(U5-RESET-Pad2)") (class "Default")
      (node (ref "U5") (pin "2") (pinfunction "RESET_2") (pintype "input"))
    )
    (net (code "109") (name "unconnected-(U5-VBAT-Pad53)") (class "Default")
      (node (ref "U5") (pin "53") (pinfunction "VBAT_53") (pintype "input"))
    )
    (net (code "110") (name "unconnected-(U5-VREF-Pad28)") (class "Default")
      (node (ref "U5") (pin "28") (pinfunction "VREF_28") (pintype "input"))
    )
  )
)
